# M101A.net
KiCad netlist of a schematic drawn in EAGLE
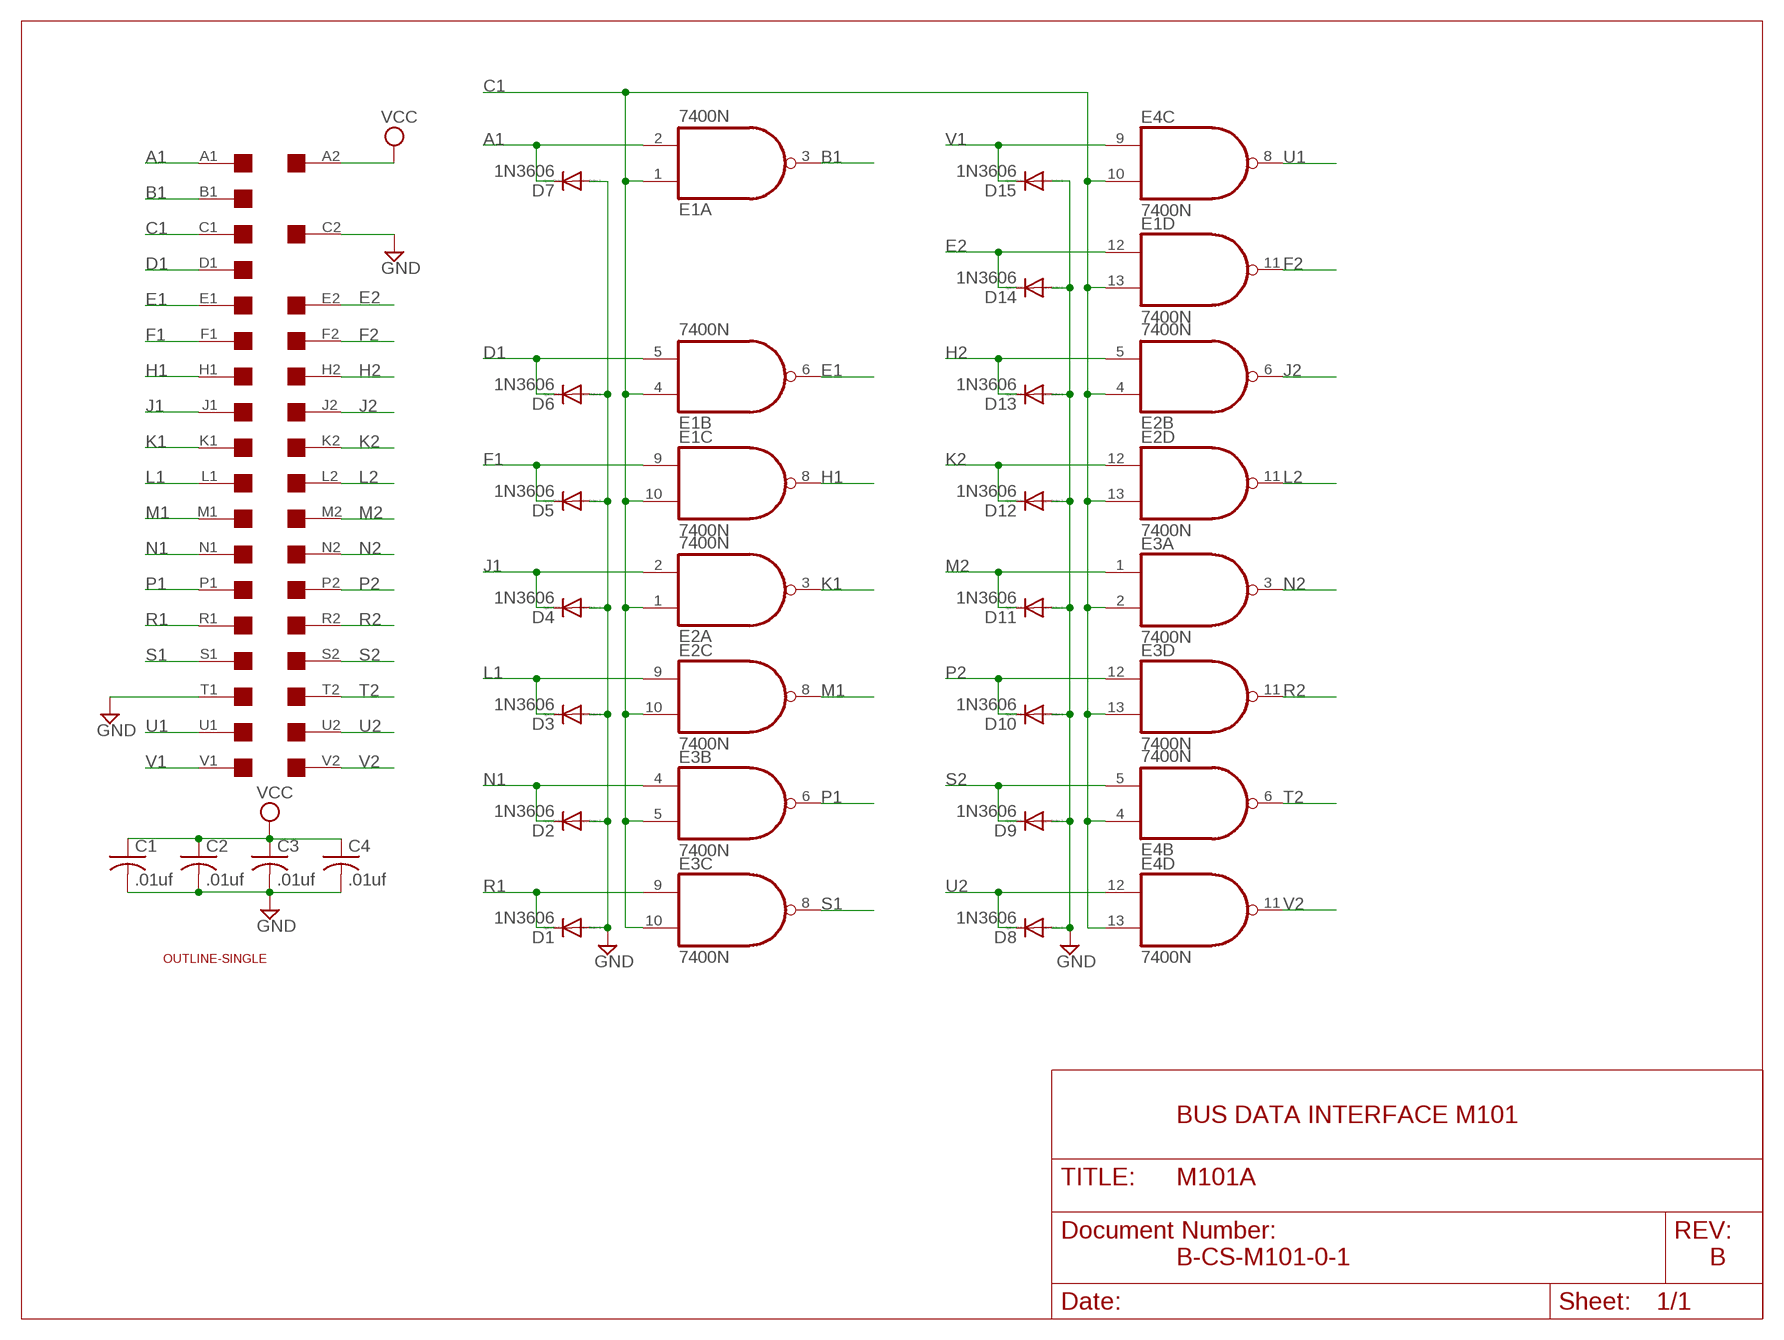
[diagram p0: schematic, sheet 1]

(export (version "E")
  (design (tool "Eeschema 10.0.6"))
  (components
    (comp (ref "C1")
      (value ".01uf")
      (footprint "eagle-import:C050-025X075")
      (libsource (lib "eagle-import") (part "C-US050-025X075"))
    )
    (comp (ref "C2")
      (value ".01uf")
      (footprint "eagle-import:C050-025X075")
      (libsource (lib "eagle-import") (part "C-US050-025X075"))
    )
    (comp (ref "C3")
      (value ".01uf")
      (footprint "eagle-import:C050-025X075")
      (libsource (lib "eagle-import") (part "C-US050-025X075"))
    )
    (comp (ref "C4")
      (value ".01uf")
      (footprint "eagle-import:C050-025X075")
      (libsource (lib "eagle-import") (part "C-US050-025X075"))
    )
    (comp (ref "D1")
      (value "1N3606")
      (footprint "eagle-import:DO35-10")
      (libsource (lib "eagle-import") (part "1N4148DO35-10"))
    )
    (comp (ref "D2")
      (value "1N3606")
      (footprint "eagle-import:DO35-10")
      (libsource (lib "eagle-import") (part "1N4148DO35-10"))
    )
    (comp (ref "D3")
      (value "1N3606")
      (footprint "eagle-import:DO35-10")
      (libsource (lib "eagle-import") (part "1N4148DO35-10"))
    )
    (comp (ref "D4")
      (value "1N3606")
      (footprint "eagle-import:DO35-10")
      (libsource (lib "eagle-import") (part "1N4148DO35-10"))
    )
    (comp (ref "D5")
      (value "1N3606")
      (footprint "eagle-import:DO35-10")
      (libsource (lib "eagle-import") (part "1N4148DO35-10"))
    )
    (comp (ref "D6")
      (value "1N3606")
      (footprint "eagle-import:DO35-10")
      (libsource (lib "eagle-import") (part "1N4148DO35-10"))
    )
    (comp (ref "D7")
      (value "1N3606")
      (footprint "eagle-import:DO35-10")
      (libsource (lib "eagle-import") (part "1N4148DO35-10"))
    )
    (comp (ref "D8")
      (value "1N3606")
      (footprint "eagle-import:DO35-10")
      (libsource (lib "eagle-import") (part "1N4148DO35-10"))
    )
    (comp (ref "D9")
      (value "1N3606")
      (footprint "eagle-import:DO35-10")
      (libsource (lib "eagle-import") (part "1N4148DO35-10"))
    )
    (comp (ref "D10")
      (value "1N3606")
      (footprint "eagle-import:DO35-10")
      (libsource (lib "eagle-import") (part "1N4148DO35-10"))
    )
    (comp (ref "D11")
      (value "1N3606")
      (footprint "eagle-import:DO35-10")
      (libsource (lib "eagle-import") (part "1N4148DO35-10"))
    )
    (comp (ref "D12")
      (value "1N3606")
      (footprint "eagle-import:DO35-10")
      (libsource (lib "eagle-import") (part "1N4148DO35-10"))
    )
    (comp (ref "D13")
      (value "1N3606")
      (footprint "eagle-import:DO35-10")
      (libsource (lib "eagle-import") (part "1N4148DO35-10"))
    )
    (comp (ref "D14")
      (value "1N3606")
      (footprint "eagle-import:DO35-10")
      (libsource (lib "eagle-import") (part "1N4148DO35-10"))
    )
    (comp (ref "D15")
      (value "1N3606")
      (footprint "eagle-import:DO35-10")
      (libsource (lib "eagle-import") (part "1N4148DO35-10"))
    )
    (comp (ref "E1")
      (value "7400N")
      (footprint "eagle-import:DIL14")
      (libsource (lib "eagle-import") (part "7400N"))
    )
    (comp (ref "E2")
      (value "7400N")
      (footprint "eagle-import:DIL14")
      (libsource (lib "eagle-import") (part "7400N"))
    )
    (comp (ref "E3")
      (value "7400N")
      (footprint "eagle-import:DIL14")
      (libsource (lib "eagle-import") (part "7400N"))
    )
    (comp (ref "E4")
      (value "7400N")
      (footprint "eagle-import:DIL14")
      (libsource (lib "eagle-import") (part "7400N"))
    )
    (comp (ref "U$1")
      (value "SINGLE")
      (footprint "eagle-import:EDGE-CON2")
      (libsource (lib "eagle-import") (part "SINGLE"))
    )
    (comp (ref "U$4")
      (value "OUTLINE-SINGLE")
      (footprint "eagle-import:SINGLE")
      (libsource (lib "eagle-import") (part "OUTLINE-SINGLE"))
    )
  )
  (nets
    (net (code "1") (name "/A1") (class "Default")
      (node (ref "D7") (pin "C") (pinfunction "C_C") (pintype "passive"))
      (node (ref "E1") (pin "2") (pinfunction "I1_2") (pintype "input"))
      (node (ref "U$1") (pin "A1") (pinfunction "1_A1") (pintype "bidirectional"))
    )
    (net (code "2") (name "/B1") (class "Default")
      (node (ref "E1") (pin "3") (pinfunction "O_3") (pintype "output"))
      (node (ref "U$1") (pin "B1") (pinfunction "1_B1") (pintype "bidirectional"))
    )
    (net (code "3") (name "/C1") (class "Default")
      (node (ref "E1") (pin "1") (pinfunction "I0_1") (pintype "input"))
      (node (ref "E1") (pin "10") (pinfunction "I1_10") (pintype "input"))
      (node (ref "E1") (pin "13") (pinfunction "I1_13") (pintype "input"))
      (node (ref "E1") (pin "4") (pinfunction "I0_4") (pintype "input"))
      (node (ref "E2") (pin "1") (pinfunction "I0_1") (pintype "input"))
      (node (ref "E2") (pin "10") (pinfunction "I1_10") (pintype "input"))
      (node (ref "E2") (pin "13") (pinfunction "I1_13") (pintype "input"))
      (node (ref "E2") (pin "4") (pinfunction "I0_4") (pintype "input"))
      (node (ref "E3") (pin "10") (pinfunction "I1_10") (pintype "input"))
      (node (ref "E3") (pin "13") (pinfunction "I1_13") (pintype "input"))
      (node (ref "E3") (pin "2") (pinfunction "I1_2") (pintype "input"))
      (node (ref "E3") (pin "5") (pinfunction "I1_5") (pintype "input"))
      (node (ref "E4") (pin "10") (pinfunction "I1_10") (pintype "input"))
      (node (ref "E4") (pin "13") (pinfunction "I1_13") (pintype "input"))
      (node (ref "E4") (pin "4") (pinfunction "I0_4") (pintype "input"))
      (node (ref "U$1") (pin "C1") (pinfunction "1_C1") (pintype "bidirectional"))
    )
    (net (code "4") (name "/D1") (class "Default")
      (node (ref "D6") (pin "C") (pinfunction "C_C") (pintype "passive"))
      (node (ref "E1") (pin "5") (pinfunction "I1_5") (pintype "input"))
      (node (ref "U$1") (pin "D1") (pinfunction "1_D1") (pintype "bidirectional"))
    )
    (net (code "5") (name "/E1") (class "Default")
      (node (ref "E1") (pin "6") (pinfunction "O_6") (pintype "output"))
      (node (ref "U$1") (pin "E1") (pinfunction "1_E1") (pintype "bidirectional"))
    )
    (net (code "6") (name "/E2") (class "Default")
      (node (ref "D14") (pin "C") (pinfunction "C_C") (pintype "passive"))
      (node (ref "E1") (pin "12") (pinfunction "I0_12") (pintype "input"))
      (node (ref "U$1") (pin "E2") (pinfunction "1_E2") (pintype "bidirectional"))
    )
    (net (code "7") (name "/F1") (class "Default")
      (node (ref "D5") (pin "C") (pinfunction "C_C") (pintype "passive"))
      (node (ref "E1") (pin "9") (pinfunction "I0_9") (pintype "input"))
      (node (ref "U$1") (pin "F1") (pinfunction "1_F1") (pintype "bidirectional"))
    )
    (net (code "8") (name "/F2") (class "Default")
      (node (ref "E1") (pin "11") (pinfunction "O_11") (pintype "output"))
      (node (ref "U$1") (pin "F2") (pinfunction "1_F2") (pintype "bidirectional"))
    )
    (net (code "9") (name "/H1") (class "Default")
      (node (ref "E1") (pin "8") (pinfunction "O_8") (pintype "output"))
      (node (ref "U$1") (pin "H1") (pinfunction "1_H1") (pintype "bidirectional"))
    )
    (net (code "10") (name "/H2") (class "Default")
      (node (ref "D13") (pin "C") (pinfunction "C_C") (pintype "passive"))
      (node (ref "E2") (pin "5") (pinfunction "I1_5") (pintype "input"))
      (node (ref "U$1") (pin "H2") (pinfunction "1_H2") (pintype "bidirectional"))
    )
    (net (code "11") (name "/J1") (class "Default")
      (node (ref "D4") (pin "C") (pinfunction "C_C") (pintype "passive"))
      (node (ref "E2") (pin "2") (pinfunction "I1_2") (pintype "input"))
      (node (ref "U$1") (pin "J1") (pinfunction "1_J1") (pintype "bidirectional"))
    )
    (net (code "12") (name "/J2") (class "Default")
      (node (ref "E2") (pin "6") (pinfunction "O_6") (pintype "output"))
      (node (ref "U$1") (pin "J2") (pinfunction "1_J2") (pintype "bidirectional"))
    )
    (net (code "13") (name "/K1") (class "Default")
      (node (ref "E2") (pin "3") (pinfunction "O_3") (pintype "output"))
      (node (ref "U$1") (pin "K1") (pinfunction "1_K1") (pintype "bidirectional"))
    )
    (net (code "14") (name "/K2") (class "Default")
      (node (ref "D12") (pin "C") (pinfunction "C_C") (pintype "passive"))
      (node (ref "E2") (pin "12") (pinfunction "I0_12") (pintype "input"))
      (node (ref "U$1") (pin "K2") (pinfunction "1_K2") (pintype "bidirectional"))
    )
    (net (code "15") (name "/L1") (class "Default")
      (node (ref "D3") (pin "C") (pinfunction "C_C") (pintype "passive"))
      (node (ref "E2") (pin "9") (pinfunction "I0_9") (pintype "input"))
      (node (ref "U$1") (pin "L1") (pinfunction "1_L1") (pintype "bidirectional"))
    )
    (net (code "16") (name "/L2") (class "Default")
      (node (ref "E2") (pin "11") (pinfunction "O_11") (pintype "output"))
      (node (ref "U$1") (pin "L2") (pinfunction "1_L2") (pintype "bidirectional"))
    )
    (net (code "17") (name "/M1") (class "Default")
      (node (ref "E2") (pin "8") (pinfunction "O_8") (pintype "output"))
      (node (ref "U$1") (pin "M1") (pinfunction "1_M1") (pintype "bidirectional"))
    )
    (net (code "18") (name "/M2") (class "Default")
      (node (ref "D11") (pin "C") (pinfunction "C_C") (pintype "passive"))
      (node (ref "E3") (pin "1") (pinfunction "I0_1") (pintype "input"))
      (node (ref "U$1") (pin "M2") (pinfunction "1_M2") (pintype "bidirectional"))
    )
    (net (code "19") (name "/N1") (class "Default")
      (node (ref "D2") (pin "C") (pinfunction "C_C") (pintype "passive"))
      (node (ref "E3") (pin "4") (pinfunction "I0_4") (pintype "input"))
      (node (ref "U$1") (pin "N1") (pinfunction "1_N1") (pintype "bidirectional"))
    )
    (net (code "20") (name "/N2") (class "Default")
      (node (ref "E3") (pin "3") (pinfunction "O_3") (pintype "output"))
      (node (ref "U$1") (pin "N2") (pinfunction "1_N2") (pintype "bidirectional"))
    )
    (net (code "21") (name "/P1") (class "Default")
      (node (ref "E3") (pin "6") (pinfunction "O_6") (pintype "output"))
      (node (ref "U$1") (pin "P1") (pinfunction "1_P1") (pintype "bidirectional"))
    )
    (net (code "22") (name "/P2") (class "Default")
      (node (ref "D10") (pin "C") (pinfunction "C_C") (pintype "passive"))
      (node (ref "E3") (pin "12") (pinfunction "I0_12") (pintype "input"))
      (node (ref "U$1") (pin "P2") (pinfunction "1_P2") (pintype "bidirectional"))
    )
    (net (code "23") (name "/R1") (class "Default")
      (node (ref "D1") (pin "C") (pinfunction "C_C") (pintype "passive"))
      (node (ref "E3") (pin "9") (pinfunction "I0_9") (pintype "input"))
      (node (ref "U$1") (pin "R1") (pinfunction "1_R1") (pintype "bidirectional"))
    )
    (net (code "24") (name "/R2") (class "Default")
      (node (ref "E3") (pin "11") (pinfunction "O_11") (pintype "output"))
      (node (ref "U$1") (pin "R2") (pinfunction "1_R2") (pintype "bidirectional"))
    )
    (net (code "25") (name "/S1") (class "Default")
      (node (ref "E3") (pin "8") (pinfunction "O_8") (pintype "output"))
      (node (ref "U$1") (pin "S1") (pinfunction "1_S1") (pintype "bidirectional"))
    )
    (net (code "26") (name "/S2") (class "Default")
      (node (ref "D9") (pin "C") (pinfunction "C_C") (pintype "passive"))
      (node (ref "E4") (pin "5") (pinfunction "I1_5") (pintype "input"))
      (node (ref "U$1") (pin "S2") (pinfunction "1_S2") (pintype "bidirectional"))
    )
    (net (code "27") (name "/T2") (class "Default")
      (node (ref "E4") (pin "6") (pinfunction "O_6") (pintype "output"))
      (node (ref "U$1") (pin "T2") (pinfunction "1_T2") (pintype "bidirectional"))
    )
    (net (code "28") (name "/U1") (class "Default")
      (node (ref "E4") (pin "8") (pinfunction "O_8") (pintype "output"))
      (node (ref "U$1") (pin "U1") (pinfunction "1_U1") (pintype "bidirectional"))
    )
    (net (code "29") (name "/U2") (class "Default")
      (node (ref "D8") (pin "C") (pinfunction "C_C") (pintype "passive"))
      (node (ref "E4") (pin "12") (pinfunction "I0_12") (pintype "input"))
      (node (ref "U$1") (pin "U2") (pinfunction "1_U2") (pintype "bidirectional"))
    )
    (net (code "30") (name "/V1") (class "Default")
      (node (ref "D15") (pin "C") (pinfunction "C_C") (pintype "passive"))
      (node (ref "E4") (pin "9") (pinfunction "I0_9") (pintype "input"))
      (node (ref "U$1") (pin "V1") (pinfunction "1_V1") (pintype "bidirectional"))
    )
    (net (code "31") (name "/V2") (class "Default")
      (node (ref "E4") (pin "11") (pinfunction "O_11") (pintype "output"))
      (node (ref "U$1") (pin "V2") (pinfunction "1_V2") (pintype "bidirectional"))
    )
    (net (code "32") (name "GND") (class "Default")
      (node (ref "C1") (pin "2") (pinfunction "2_2") (pintype "passive"))
      (node (ref "C2") (pin "2") (pinfunction "2_2") (pintype "passive"))
      (node (ref "C3") (pin "2") (pinfunction "2_2") (pintype "passive"))
      (node (ref "C4") (pin "2") (pinfunction "2_2") (pintype "passive"))
      (node (ref "D1") (pin "A") (pinfunction "A_A") (pintype "passive"))
      (node (ref "D10") (pin "A") (pinfunction "A_A") (pintype "passive"))
      (node (ref "D11") (pin "A") (pinfunction "A_A") (pintype "passive"))
      (node (ref "D12") (pin "A") (pinfunction "A_A") (pintype "passive"))
      (node (ref "D13") (pin "A") (pinfunction "A_A") (pintype "passive"))
      (node (ref "D14") (pin "A") (pinfunction "A_A") (pintype "passive"))
      (node (ref "D15") (pin "A") (pinfunction "A_A") (pintype "passive"))
      (node (ref "D2") (pin "A") (pinfunction "A_A") (pintype "passive"))
      (node (ref "D3") (pin "A") (pinfunction "A_A") (pintype "passive"))
      (node (ref "D4") (pin "A") (pinfunction "A_A") (pintype "passive"))
      (node (ref "D5") (pin "A") (pinfunction "A_A") (pintype "passive"))
      (node (ref "D6") (pin "A") (pinfunction "A_A") (pintype "passive"))
      (node (ref "D7") (pin "A") (pinfunction "A_A") (pintype "passive"))
      (node (ref "D8") (pin "A") (pinfunction "A_A") (pintype "passive"))
      (node (ref "D9") (pin "A") (pinfunction "A_A") (pintype "passive"))
      (node (ref "U$1") (pin "C2") (pinfunction "1_C2") (pintype "bidirectional"))
      (node (ref "U$1") (pin "T1") (pinfunction "1_T1") (pintype "bidirectional"))
    )
    (net (code "33") (name "VCC") (class "Default")
      (node (ref "C1") (pin "1") (pinfunction "1_1") (pintype "passive"))
      (node (ref "C2") (pin "1") (pinfunction "1_1") (pintype "passive"))
      (node (ref "C3") (pin "1") (pinfunction "1_1") (pintype "passive"))
      (node (ref "C4") (pin "1") (pinfunction "1_1") (pintype "passive"))
      (node (ref "U$1") (pin "A2") (pinfunction "1_A2") (pintype "bidirectional"))
    )
  )
)
